# pic16f877a_de.net
KiCad netlist of a schematic drawn in EAGLE
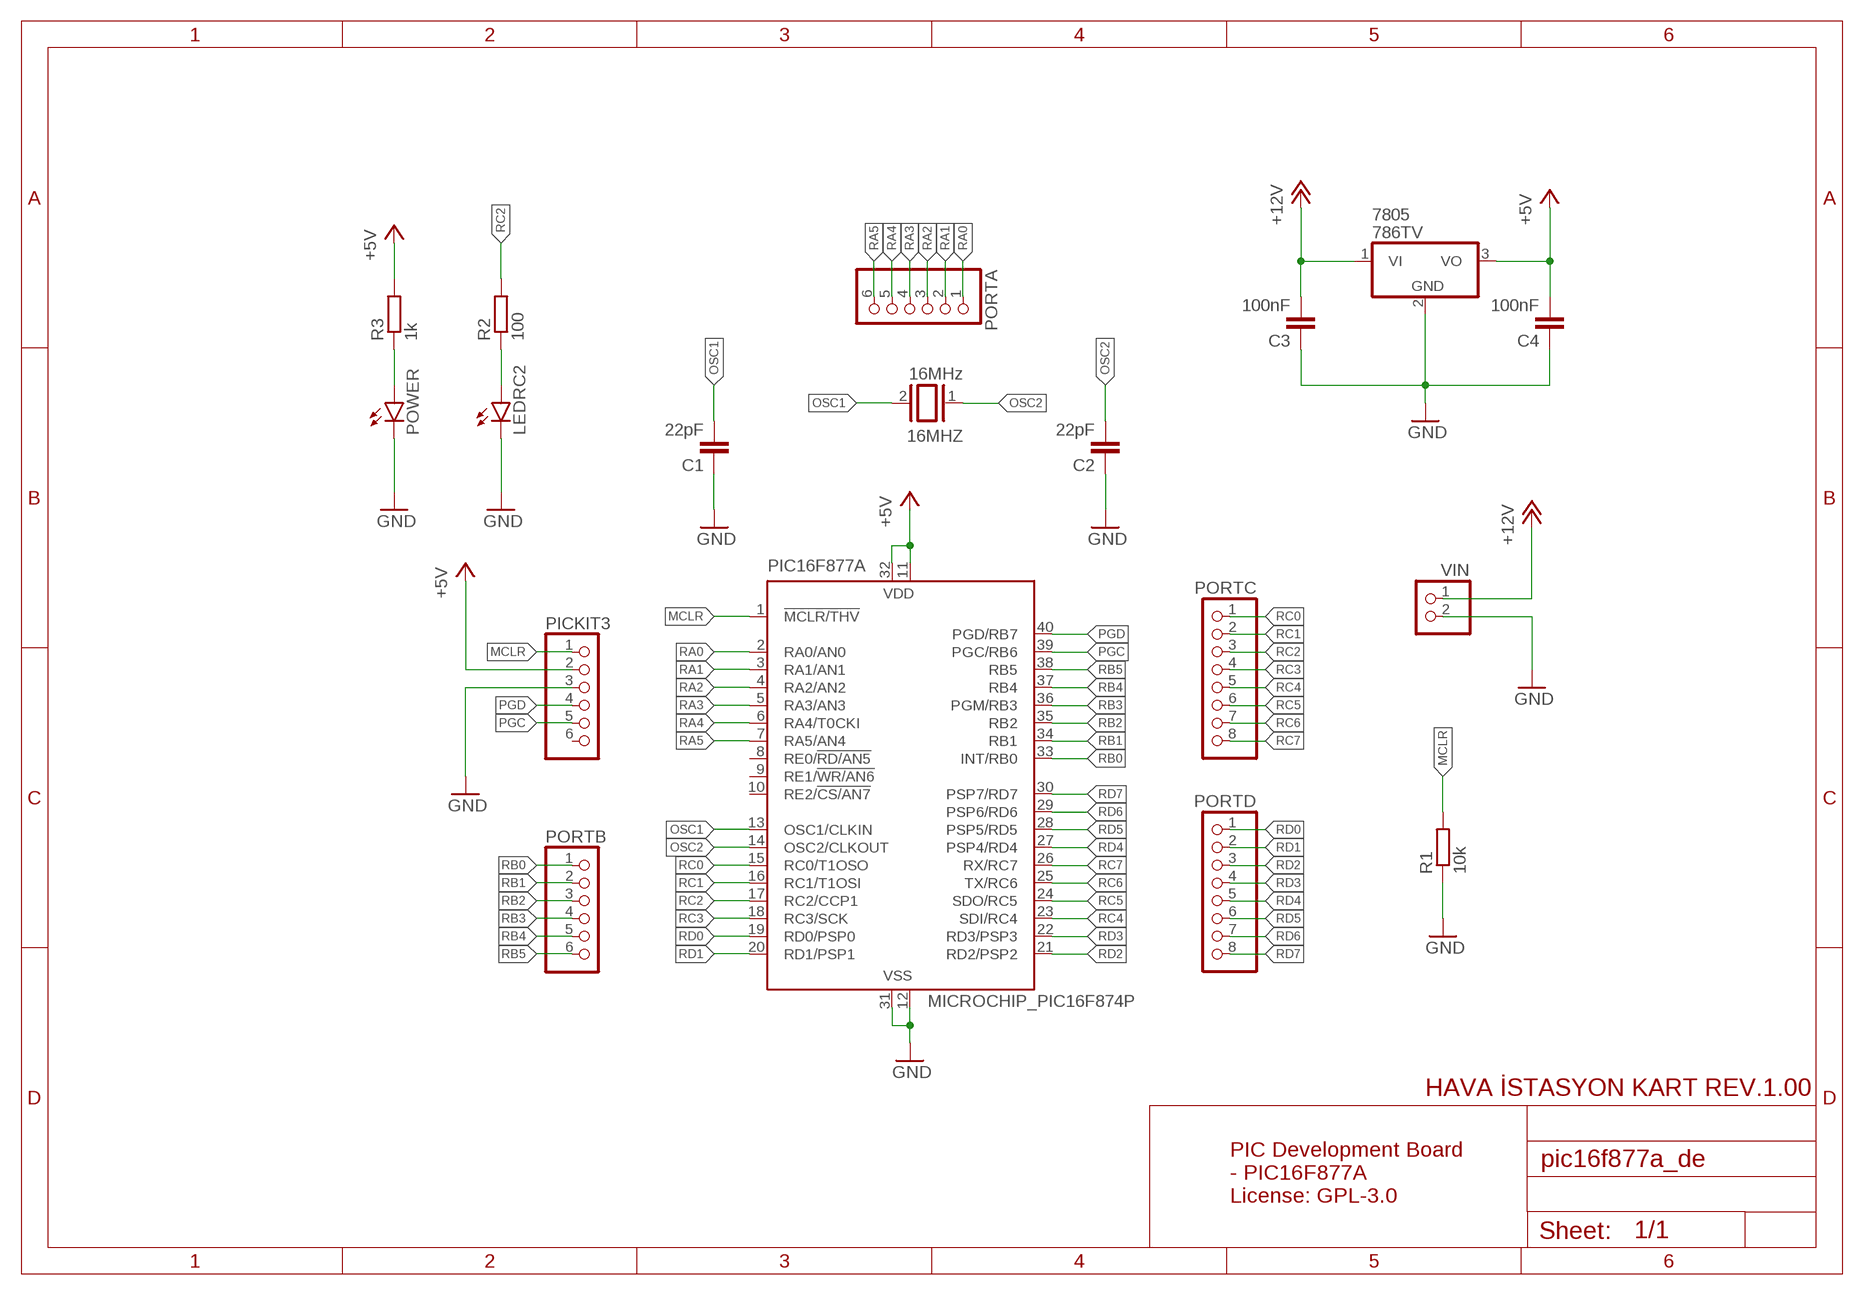
[diagram p0: schematic, sheet 1]

(export (version "E")
  (design (tool "Eeschema 10.0.6"))
  (components
    (comp (ref "16MHZ")
      (value "16MHz")
      (footprint "eagle-import:QS")
      (libsource (lib "eagle-import") (part "XTAL/S"))
    )
    (comp (ref "7805")
      (value "786TV")
      (footprint "eagle-import:TO220V")
      (libsource (lib "eagle-import") (part "78TV6"))
    )
    (comp (ref "C1")
      (value "22pF")
      (footprint "eagle-import:C025-025X050")
      (libsource (lib "eagle-import") (part "C-EU025-025X050"))
    )
    (comp (ref "C2")
      (value "22pF")
      (footprint "eagle-import:C025-025X050")
      (libsource (lib "eagle-import") (part "C-EU025-025X050"))
    )
    (comp (ref "C3")
      (value "100nF")
      (footprint "eagle-import:C025-025X050")
      (libsource (lib "eagle-import") (part "C-EU025-025X050"))
    )
    (comp (ref "C4")
      (value "100nF")
      (footprint "eagle-import:C025-025X050")
      (libsource (lib "eagle-import") (part "C-EU025-025X050"))
    )
    (comp (ref "LEDRC2")
      (value "LED5MM")
      (footprint "eagle-import:LED5MM")
      (libsource (lib "eagle-import") (part "LED5MM"))
    )
    (comp (ref "PIC16F877A")
      (value "MICROCHIP_PIC16F874P")
      (footprint "eagle-import:MICROCHIP_DIL40")
      (fields (field (name "MPN") "PIC16F874-04I/P"))
      (libsource (lib "eagle-import") (part "MICROCHIP_PIC16F87P4"))
    )
    (comp (ref "PICKIT3")
      (value "PINHD-1X6")
      (footprint "eagle-import:1X06")
      (libsource (lib "eagle-import") (part "PINHD-1X6"))
    )
    (comp (ref "PORTA")
      (value "PINHD-1X6")
      (footprint "eagle-import:1X06")
      (libsource (lib "eagle-import") (part "PINHD-1X6"))
    )
    (comp (ref "PORTB")
      (value "PINHD-1X6")
      (footprint "eagle-import:1X06")
      (libsource (lib "eagle-import") (part "PINHD-1X6"))
    )
    (comp (ref "PORTC")
      (value "PINHD-1X8")
      (footprint "eagle-import:1X08")
      (libsource (lib "eagle-import") (part "PINHD-1X8"))
    )
    (comp (ref "PORTD")
      (value "PINHD-1X8")
      (footprint "eagle-import:1X08")
      (libsource (lib "eagle-import") (part "PINHD-1X8"))
    )
    (comp (ref "POWER")
      (value "LED5MM")
      (footprint "eagle-import:LED5MM")
      (libsource (lib "eagle-import") (part "LED5MM"))
    )
    (comp (ref "R1")
      (value "10k")
      (footprint "eagle-import:0207_7")
      (libsource (lib "eagle-import") (part "R-EU_0207/7"))
    )
    (comp (ref "R2")
      (value "100")
      (footprint "eagle-import:0207_7")
      (libsource (lib "eagle-import") (part "R-EU_0207/7"))
    )
    (comp (ref "R3")
      (value "1k")
      (footprint "eagle-import:0207_7")
      (libsource (lib "eagle-import") (part "R-EU_0207/7"))
    )
    (comp (ref "VIN")
      (value "PINHD-1X2")
      (footprint "eagle-import:1X02")
      (libsource (lib "eagle-import") (part "PINHD-1X2"))
    )
  )
  (nets
    (net (code "1") (name "+5V") (class "Default")
      (node (ref "7805") (pin "3") (pinfunction "VO_3") (pintype "passive"))
      (node (ref "C4") (pin "2") (pinfunction "2_2") (pintype "passive"))
      (node (ref "PIC16F877A") (pin "11") (pinfunction "VDD_11") (pintype "power_in"))
      (node (ref "PIC16F877A") (pin "32") (pinfunction "VDD_32") (pintype "power_in"))
      (node (ref "PICKIT3") (pin "2") (pinfunction "2_2") (pintype "passive"))
      (node (ref "R3") (pin "2") (pinfunction "2_2") (pintype "passive"))
    )
    (net (code "2") (name "+12V") (class "Default")
      (node (ref "7805") (pin "1") (pinfunction "VI_1") (pintype "input"))
      (node (ref "C3") (pin "2") (pinfunction "2_2") (pintype "passive"))
      (node (ref "VIN") (pin "1") (pinfunction "1_1") (pintype "passive"))
    )
    (net (code "3") (name "GND") (class "Default")
      (node (ref "7805") (pin "2") (pinfunction "GND_2") (pintype "passive"))
      (node (ref "C1") (pin "1") (pinfunction "1_1") (pintype "passive"))
      (node (ref "C2") (pin "1") (pinfunction "1_1") (pintype "passive"))
      (node (ref "C3") (pin "1") (pinfunction "1_1") (pintype "passive"))
      (node (ref "C4") (pin "1") (pinfunction "1_1") (pintype "passive"))
      (node (ref "LEDRC2") (pin "K") (pinfunction "C_K") (pintype "passive"))
      (node (ref "PIC16F877A") (pin "12") (pinfunction "VSS_12") (pintype "power_in"))
      (node (ref "PIC16F877A") (pin "31") (pinfunction "VSS_31") (pintype "power_in"))
      (node (ref "PICKIT3") (pin "3") (pinfunction "3_3") (pintype "passive"))
      (node (ref "POWER") (pin "K") (pinfunction "C_K") (pintype "passive"))
      (node (ref "R1") (pin "1") (pinfunction "1_1") (pintype "passive"))
      (node (ref "VIN") (pin "2") (pinfunction "2_2") (pintype "passive"))
    )
    (net (code "4") (name "MCLR") (class "Default")
      (node (ref "PIC16F877A") (pin "1") (pinfunction "~{MCLR/THV}_1") (pintype "input"))
      (node (ref "PICKIT3") (pin "1") (pinfunction "1_1") (pintype "passive"))
      (node (ref "R1") (pin "2") (pinfunction "2_2") (pintype "passive"))
    )
    (net (code "5") (name "Net-(LEDRC2-PadA)") (class "Default")
      (node (ref "LEDRC2") (pin "A") (pinfunction "A_A") (pintype "passive"))
      (node (ref "R2") (pin "1") (pinfunction "1_1") (pintype "passive"))
    )
    (net (code "6") (name "Net-(POWER-PadA)") (class "Default")
      (node (ref "POWER") (pin "A") (pinfunction "A_A") (pintype "passive"))
      (node (ref "R3") (pin "1") (pinfunction "1_1") (pintype "passive"))
    )
    (net (code "7") (name "OSC1") (class "Default")
      (node (ref "16MHZ") (pin "2") (pinfunction "2_2") (pintype "passive"))
      (node (ref "C1") (pin "2") (pinfunction "2_2") (pintype "passive"))
      (node (ref "PIC16F877A") (pin "13") (pinfunction "OSC1/CLKIN_13") (pintype "input"))
    )
    (net (code "8") (name "OSC2") (class "Default")
      (node (ref "16MHZ") (pin "1") (pinfunction "1_1") (pintype "passive"))
      (node (ref "C2") (pin "2") (pinfunction "2_2") (pintype "passive"))
      (node (ref "PIC16F877A") (pin "14") (pinfunction "OSC2/CLKOUT_14") (pintype "output"))
    )
    (net (code "9") (name "PGC") (class "Default")
      (node (ref "PIC16F877A") (pin "39") (pinfunction "PGC/RB6_39") (pintype "bidirectional"))
      (node (ref "PICKIT3") (pin "5") (pinfunction "5_5") (pintype "passive"))
    )
    (net (code "10") (name "PGD") (class "Default")
      (node (ref "PIC16F877A") (pin "40") (pinfunction "PGD/RB7_40") (pintype "bidirectional"))
      (node (ref "PICKIT3") (pin "4") (pinfunction "4_4") (pintype "passive"))
    )
    (net (code "11") (name "RA0") (class "Default")
      (node (ref "PIC16F877A") (pin "2") (pinfunction "RA0/AN0_2") (pintype "bidirectional"))
      (node (ref "PORTA") (pin "1") (pinfunction "1_1") (pintype "passive"))
    )
    (net (code "12") (name "RA1") (class "Default")
      (node (ref "PIC16F877A") (pin "3") (pinfunction "RA1/AN1_3") (pintype "bidirectional"))
      (node (ref "PORTA") (pin "2") (pinfunction "2_2") (pintype "passive"))
    )
    (net (code "13") (name "RA2") (class "Default")
      (node (ref "PIC16F877A") (pin "4") (pinfunction "RA2/AN2_4") (pintype "bidirectional"))
      (node (ref "PORTA") (pin "3") (pinfunction "3_3") (pintype "passive"))
    )
    (net (code "14") (name "RA3") (class "Default")
      (node (ref "PIC16F877A") (pin "5") (pinfunction "RA3/AN3_5") (pintype "bidirectional"))
      (node (ref "PORTA") (pin "4") (pinfunction "4_4") (pintype "passive"))
    )
    (net (code "15") (name "RA4") (class "Default")
      (node (ref "PIC16F877A") (pin "6") (pinfunction "RA4/T0CKI_6") (pintype "bidirectional"))
      (node (ref "PORTA") (pin "5") (pinfunction "5_5") (pintype "passive"))
    )
    (net (code "16") (name "RA5") (class "Default")
      (node (ref "PIC16F877A") (pin "7") (pinfunction "RA5/AN4_7") (pintype "bidirectional"))
      (node (ref "PORTA") (pin "6") (pinfunction "6_6") (pintype "passive"))
    )
    (net (code "17") (name "RB0") (class "Default")
      (node (ref "PIC16F877A") (pin "33") (pinfunction "INT/RB0_33") (pintype "bidirectional"))
      (node (ref "PORTB") (pin "1") (pinfunction "1_1") (pintype "passive"))
    )
    (net (code "18") (name "RB1") (class "Default")
      (node (ref "PIC16F877A") (pin "34") (pinfunction "RB1_34") (pintype "bidirectional"))
      (node (ref "PORTB") (pin "2") (pinfunction "2_2") (pintype "passive"))
    )
    (net (code "19") (name "RB2") (class "Default")
      (node (ref "PIC16F877A") (pin "35") (pinfunction "RB2_35") (pintype "bidirectional"))
      (node (ref "PORTB") (pin "3") (pinfunction "3_3") (pintype "passive"))
    )
    (net (code "20") (name "RB3") (class "Default")
      (node (ref "PIC16F877A") (pin "36") (pinfunction "PGM/RB3_36") (pintype "bidirectional"))
      (node (ref "PORTB") (pin "4") (pinfunction "4_4") (pintype "passive"))
    )
    (net (code "21") (name "RB4") (class "Default")
      (node (ref "PIC16F877A") (pin "37") (pinfunction "RB4_37") (pintype "bidirectional"))
      (node (ref "PORTB") (pin "5") (pinfunction "5_5") (pintype "passive"))
    )
    (net (code "22") (name "RB5") (class "Default")
      (node (ref "PIC16F877A") (pin "38") (pinfunction "RB5_38") (pintype "bidirectional"))
      (node (ref "PORTB") (pin "6") (pinfunction "6_6") (pintype "passive"))
    )
    (net (code "23") (name "RC0") (class "Default")
      (node (ref "PIC16F877A") (pin "15") (pinfunction "RC0/T1OSO_15") (pintype "bidirectional"))
      (node (ref "PORTC") (pin "1") (pinfunction "1_1") (pintype "passive"))
    )
    (net (code "24") (name "RC1") (class "Default")
      (node (ref "PIC16F877A") (pin "16") (pinfunction "RC1/T1OSI_16") (pintype "bidirectional"))
      (node (ref "PORTC") (pin "2") (pinfunction "2_2") (pintype "passive"))
    )
    (net (code "25") (name "RC2") (class "Default")
      (node (ref "PIC16F877A") (pin "17") (pinfunction "RC2/CCP1_17") (pintype "bidirectional"))
      (node (ref "PORTC") (pin "3") (pinfunction "3_3") (pintype "passive"))
      (node (ref "R2") (pin "2") (pinfunction "2_2") (pintype "passive"))
    )
    (net (code "26") (name "RC3") (class "Default")
      (node (ref "PIC16F877A") (pin "18") (pinfunction "RC3/SCK_18") (pintype "bidirectional"))
      (node (ref "PORTC") (pin "4") (pinfunction "4_4") (pintype "passive"))
    )
    (net (code "27") (name "RC4") (class "Default")
      (node (ref "PIC16F877A") (pin "23") (pinfunction "SDI/RC4_23") (pintype "bidirectional"))
      (node (ref "PORTC") (pin "5") (pinfunction "5_5") (pintype "passive"))
    )
    (net (code "28") (name "RC5") (class "Default")
      (node (ref "PIC16F877A") (pin "24") (pinfunction "SDO/RC5_24") (pintype "bidirectional"))
      (node (ref "PORTC") (pin "6") (pinfunction "6_6") (pintype "passive"))
    )
    (net (code "29") (name "RC6") (class "Default")
      (node (ref "PIC16F877A") (pin "25") (pinfunction "TX/RC6_25") (pintype "bidirectional"))
      (node (ref "PORTC") (pin "7") (pinfunction "7_7") (pintype "passive"))
    )
    (net (code "30") (name "RC7") (class "Default")
      (node (ref "PIC16F877A") (pin "26") (pinfunction "RX/RC7_26") (pintype "bidirectional"))
      (node (ref "PORTC") (pin "8") (pinfunction "8_8") (pintype "passive"))
    )
    (net (code "31") (name "RD0") (class "Default")
      (node (ref "PIC16F877A") (pin "19") (pinfunction "RD0/PSP0_19") (pintype "bidirectional"))
      (node (ref "PORTD") (pin "1") (pinfunction "1_1") (pintype "passive"))
    )
    (net (code "32") (name "RD1") (class "Default")
      (node (ref "PIC16F877A") (pin "20") (pinfunction "RD1/PSP1_20") (pintype "bidirectional"))
      (node (ref "PORTD") (pin "2") (pinfunction "2_2") (pintype "passive"))
    )
    (net (code "33") (name "RD2") (class "Default")
      (node (ref "PIC16F877A") (pin "21") (pinfunction "RD2/PSP2_21") (pintype "bidirectional"))
      (node (ref "PORTD") (pin "3") (pinfunction "3_3") (pintype "passive"))
    )
    (net (code "34") (name "RD3") (class "Default")
      (node (ref "PIC16F877A") (pin "22") (pinfunction "RD3/PSP3_22") (pintype "bidirectional"))
      (node (ref "PORTD") (pin "4") (pinfunction "4_4") (pintype "passive"))
    )
    (net (code "35") (name "RD4") (class "Default")
      (node (ref "PIC16F877A") (pin "27") (pinfunction "PSP4/RD4_27") (pintype "bidirectional"))
      (node (ref "PORTD") (pin "5") (pinfunction "5_5") (pintype "passive"))
    )
    (net (code "36") (name "RD5") (class "Default")
      (node (ref "PIC16F877A") (pin "28") (pinfunction "PSP5/RD5_28") (pintype "bidirectional"))
      (node (ref "PORTD") (pin "6") (pinfunction "6_6") (pintype "passive"))
    )
    (net (code "37") (name "RD6") (class "Default")
      (node (ref "PIC16F877A") (pin "29") (pinfunction "PSP6/RD6_29") (pintype "bidirectional"))
      (node (ref "PORTD") (pin "7") (pinfunction "7_7") (pintype "passive"))
    )
    (net (code "38") (name "RD7") (class "Default")
      (node (ref "PIC16F877A") (pin "30") (pinfunction "PSP7/RD7_30") (pintype "bidirectional"))
      (node (ref "PORTD") (pin "8") (pinfunction "8_8") (pintype "passive"))
    )
    (net (code "39") (name "unconnected-(PIC16F877A-RE0{slash}~{RD{slash}AN5}-Pad8)") (class "Default")
      (node (ref "PIC16F877A") (pin "8") (pinfunction "RE0/~{RD/AN5}_8") (pintype "bidirectional"))
    )
    (net (code "40") (name "unconnected-(PIC16F877A-RE1{slash}~{WR{slash}AN6}-Pad9)") (class "Default")
      (node (ref "PIC16F877A") (pin "9") (pinfunction "RE1/~{WR/AN6}_9") (pintype "bidirectional"))
    )
    (net (code "41") (name "unconnected-(PIC16F877A-RE2{slash}~{CS{slash}AN7}-Pad10)") (class "Default")
      (node (ref "PIC16F877A") (pin "10") (pinfunction "RE2/~{CS/AN7}_10") (pintype "bidirectional"))
    )
    (net (code "42") (name "unconnected-(PICKIT3-Pad6)") (class "Default")
      (node (ref "PICKIT3") (pin "6") (pinfunction "6_6") (pintype "passive"))
    )
  )
)
